# SCH_sir-kodic_2026-05-30.net
KiCad netlist of a schematic drawn in EasyEDA
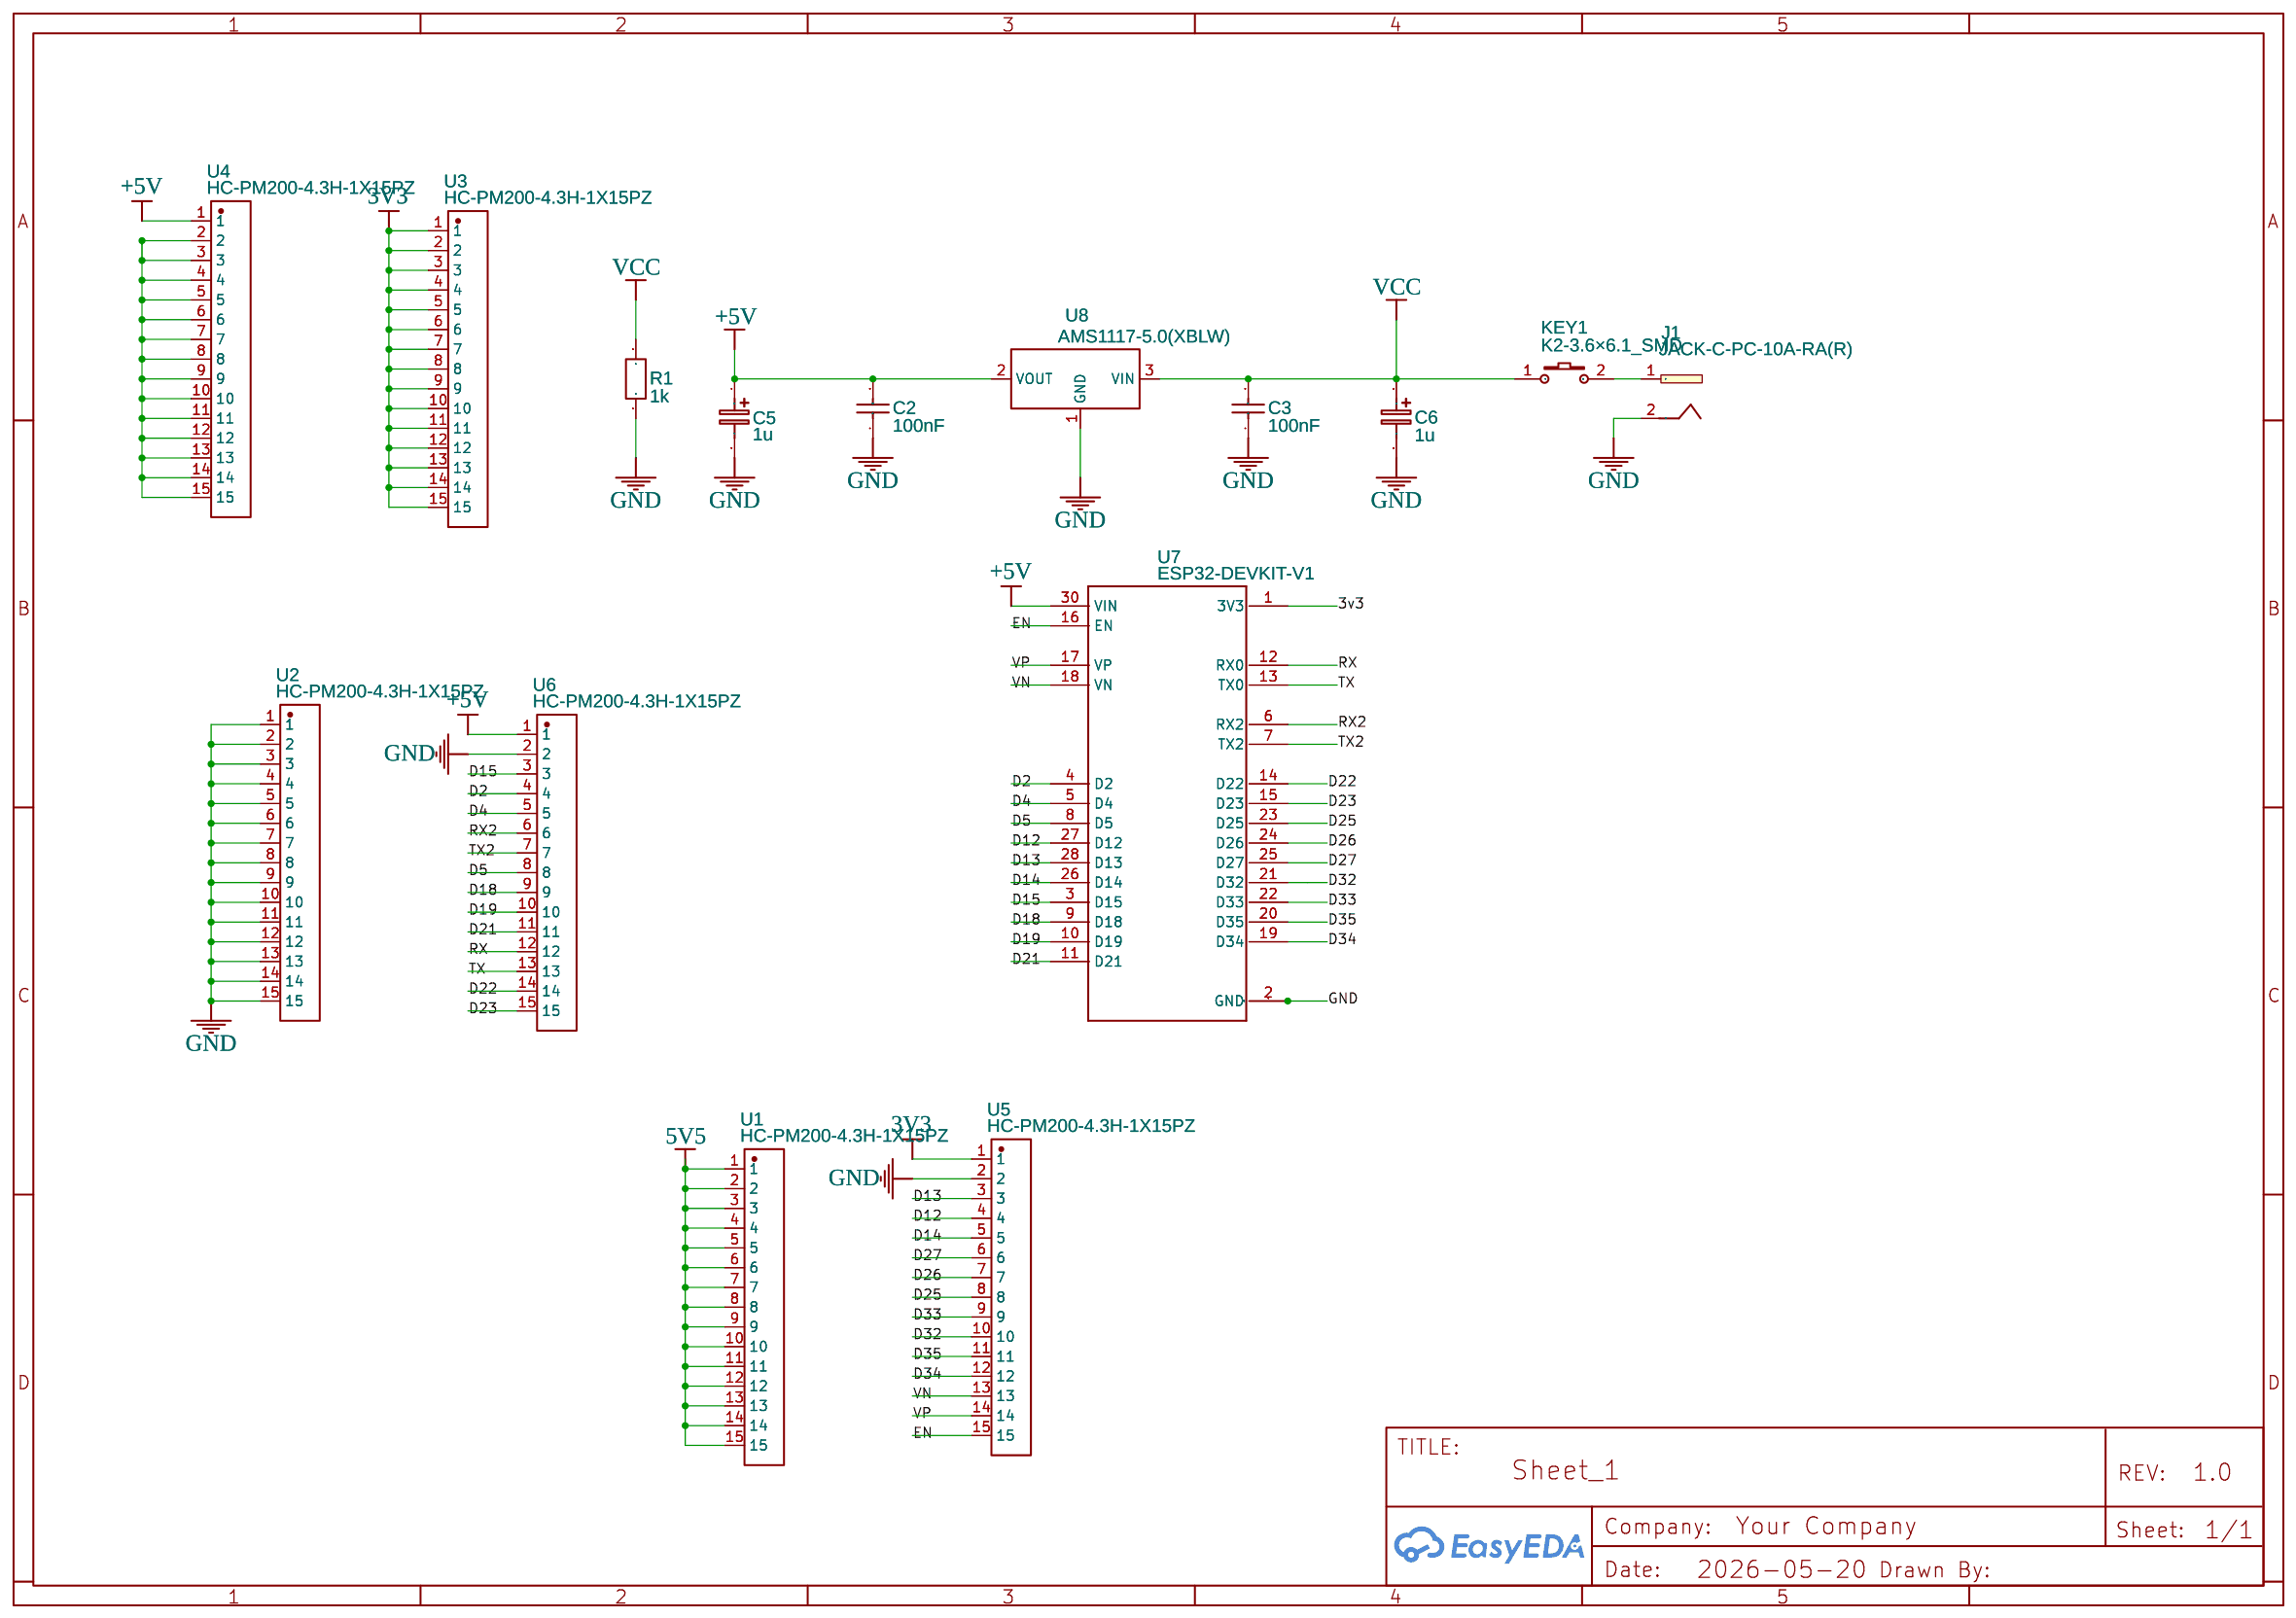
[diagram p0: schematic sheet]

(export (version "E")
  (design (tool "Eeschema 10.0.6"))
  (components
    (comp (ref "C2")
      (value "100nF")
      (fields (field (name "Manufacturer Part") "0.1UF(104) +-20% 63v"))
      (libsource (lib "") (part "100nF"))
    )
    (comp (ref "C3")
      (value "100nF")
      (fields (field (name "Manufacturer Part") "0.1UF(104) +-20% 63v"))
      (libsource (lib "") (part "100nF"))
    )
    (comp (ref "C5") (value "1u") (libsource (lib "") (part "C_Tan_SMD_A_EU")))
    (comp (ref "C6") (value "1u") (libsource (lib "") (part "C_Tan_SMD_A_EU_1")))
    (comp (ref "J1") (value "JACK-C-PC-10A-RA(R)") (libsource (lib "") (part "JACK-C-PC-10A-RA(R)")))
    (comp (ref "KEY1")
      (value "K2-3.6×6.1_SMD")
      (fields (field (name "Manufacturer Part") "K2-1107ST-A4SW-06"))
      (libsource (lib "") (part "K2-3.6×6.1_SMD"))
    )
    (comp (ref "R1") (value "1k") (libsource (lib "") (part "R_0603_EU")))
    (comp (ref "U1")
      (value "HC-PM200-4.3H-1X15PZ")
      (fields
        (field (name "Manufacturer Part") "HC-PM200-4.3H-1x15PZ")
        (field (name "Manufacturer") "HC(虹成电子)")
      )
      (libsource (lib "") (part "HC-PM200-4.3H-1X15PZ"))
    )
    (comp (ref "U2")
      (value "HC-PM200-4.3H-1X15PZ")
      (fields
        (field (name "Manufacturer Part") "HC-PM200-4.3H-1x15PZ")
        (field (name "Manufacturer") "HC(虹成电子)")
      )
      (libsource (lib "") (part "HC-PM200-4.3H-1X15PZ"))
    )
    (comp (ref "U3")
      (value "HC-PM200-4.3H-1X15PZ")
      (fields
        (field (name "Manufacturer Part") "HC-PM200-4.3H-1x15PZ")
        (field (name "Manufacturer") "HC(虹成电子)")
      )
      (libsource (lib "") (part "HC-PM200-4.3H-1X15PZ"))
    )
    (comp (ref "U4")
      (value "HC-PM200-4.3H-1X15PZ")
      (fields
        (field (name "Manufacturer Part") "HC-PM200-4.3H-1x15PZ")
        (field (name "Manufacturer") "HC(虹成电子)")
      )
      (libsource (lib "") (part "HC-PM200-4.3H-1X15PZ"))
    )
    (comp (ref "U5")
      (value "HC-PM200-4.3H-1X15PZ")
      (fields
        (field (name "Manufacturer Part") "HC-PM200-4.3H-1x15PZ")
        (field (name "Manufacturer") "HC(虹成电子)")
      )
      (libsource (lib "") (part "HC-PM200-4.3H-1X15PZ"))
    )
    (comp (ref "U6")
      (value "HC-PM200-4.3H-1X15PZ")
      (fields
        (field (name "Manufacturer Part") "HC-PM200-4.3H-1x15PZ")
        (field (name "Manufacturer") "HC(虹成电子)")
      )
      (libsource (lib "") (part "HC-PM200-4.3H-1X15PZ"))
    )
    (comp (ref "U7") (value "ESP32-DEVKIT-V1") (libsource (lib "") (part "ESP32-DEVKIT-V1")))
    (comp (ref "U8")
      (value "AMS1117-5.0(XBLW)")
      (fields (field (name "Manufacturer") "XBLW(芯伯乐)"))
      (libsource (lib "") (part "AMS1117-5.0(XBLW)"))
    )
  )
  (nets
    (net (code "1") (name "+5V") (class "Default")
      (node (ref "C2") (pin "2") (pinfunction "2_2") (pintype "input"))
      (node (ref "C5") (pin "1") (pinfunction "1_1") (pintype "unspecified"))
      (node (ref "U4") (pin "1") (pinfunction "1_1") (pintype "unspecified"))
      (node (ref "U6") (pin "1") (pinfunction "1_1") (pintype "unspecified"))
      (node (ref "U7") (pin "30") (pinfunction "VIN_30") (pintype "bidirectional"))
      (node (ref "U8") (pin "2") (pinfunction "VOUT_2") (pintype "unspecified"))
    )
    (net (code "2") (name "/3v3") (class "Default")
      (node (ref "U7") (pin "1") (pinfunction "3V3_1") (pintype "bidirectional"))
    )
    (net (code "3") (name "/D2") (class "Default")
      (node (ref "U6") (pin "4") (pinfunction "4_4") (pintype "unspecified"))
      (node (ref "U7") (pin "4") (pinfunction "D2_4") (pintype "bidirectional"))
    )
    (net (code "4") (name "/D4") (class "Default")
      (node (ref "U6") (pin "5") (pinfunction "5_5") (pintype "unspecified"))
      (node (ref "U7") (pin "5") (pinfunction "D4_5") (pintype "bidirectional"))
    )
    (net (code "5") (name "/D5") (class "Default")
      (node (ref "U6") (pin "8") (pinfunction "8_8") (pintype "unspecified"))
      (node (ref "U7") (pin "8") (pinfunction "D5_8") (pintype "bidirectional"))
    )
    (net (code "6") (name "/D12") (class "Default")
      (node (ref "U5") (pin "4") (pinfunction "4_4") (pintype "unspecified"))
      (node (ref "U7") (pin "27") (pinfunction "D12_27") (pintype "bidirectional"))
    )
    (net (code "7") (name "/D13") (class "Default")
      (node (ref "U5") (pin "3") (pinfunction "3_3") (pintype "unspecified"))
      (node (ref "U7") (pin "28") (pinfunction "D13_28") (pintype "bidirectional"))
    )
    (net (code "8") (name "/D14") (class "Default")
      (node (ref "U5") (pin "5") (pinfunction "5_5") (pintype "unspecified"))
      (node (ref "U7") (pin "26") (pinfunction "D14_26") (pintype "bidirectional"))
    )
    (net (code "9") (name "/D15") (class "Default")
      (node (ref "U6") (pin "3") (pinfunction "3_3") (pintype "unspecified"))
      (node (ref "U7") (pin "3") (pinfunction "D15_3") (pintype "bidirectional"))
    )
    (net (code "10") (name "/D18") (class "Default")
      (node (ref "U6") (pin "9") (pinfunction "9_9") (pintype "unspecified"))
      (node (ref "U7") (pin "9") (pinfunction "D18_9") (pintype "bidirectional"))
    )
    (net (code "11") (name "/D19") (class "Default")
      (node (ref "U6") (pin "10") (pinfunction "10_10") (pintype "unspecified"))
      (node (ref "U7") (pin "10") (pinfunction "D19_10") (pintype "bidirectional"))
    )
    (net (code "12") (name "/D21") (class "Default")
      (node (ref "U6") (pin "11") (pinfunction "11_11") (pintype "unspecified"))
      (node (ref "U7") (pin "11") (pinfunction "D21_11") (pintype "bidirectional"))
    )
    (net (code "13") (name "/D22") (class "Default")
      (node (ref "U6") (pin "14") (pinfunction "14_14") (pintype "unspecified"))
      (node (ref "U7") (pin "14") (pinfunction "D22_14") (pintype "bidirectional"))
    )
    (net (code "14") (name "/D23") (class "Default")
      (node (ref "U6") (pin "15") (pinfunction "15_15") (pintype "unspecified"))
      (node (ref "U7") (pin "15") (pinfunction "D23_15") (pintype "bidirectional"))
    )
    (net (code "15") (name "/D25") (class "Default")
      (node (ref "U5") (pin "8") (pinfunction "8_8") (pintype "unspecified"))
      (node (ref "U7") (pin "23") (pinfunction "D25_23") (pintype "bidirectional"))
    )
    (net (code "16") (name "/D26") (class "Default")
      (node (ref "U5") (pin "7") (pinfunction "7_7") (pintype "unspecified"))
      (node (ref "U7") (pin "24") (pinfunction "D26_24") (pintype "bidirectional"))
    )
    (net (code "17") (name "/D27") (class "Default")
      (node (ref "U5") (pin "6") (pinfunction "6_6") (pintype "unspecified"))
      (node (ref "U7") (pin "25") (pinfunction "D27_25") (pintype "bidirectional"))
    )
    (net (code "18") (name "/D32") (class "Default")
      (node (ref "U5") (pin "10") (pinfunction "10_10") (pintype "unspecified"))
      (node (ref "U7") (pin "21") (pinfunction "D32_21") (pintype "bidirectional"))
    )
    (net (code "19") (name "/D33") (class "Default")
      (node (ref "U5") (pin "9") (pinfunction "9_9") (pintype "unspecified"))
      (node (ref "U7") (pin "22") (pinfunction "D33_22") (pintype "bidirectional"))
    )
    (net (code "20") (name "/D34") (class "Default")
      (node (ref "U5") (pin "12") (pinfunction "12_12") (pintype "unspecified"))
      (node (ref "U7") (pin "19") (pinfunction "D34_19") (pintype "bidirectional"))
    )
    (net (code "21") (name "/D35") (class "Default")
      (node (ref "U5") (pin "11") (pinfunction "11_11") (pintype "unspecified"))
      (node (ref "U7") (pin "20") (pinfunction "D35_20") (pintype "bidirectional"))
    )
    (net (code "22") (name "/EN") (class "Default")
      (node (ref "U5") (pin "15") (pinfunction "15_15") (pintype "unspecified"))
      (node (ref "U7") (pin "16") (pinfunction "EN_16") (pintype "bidirectional"))
    )
    (net (code "23") (name "/RX") (class "Default")
      (node (ref "U6") (pin "12") (pinfunction "12_12") (pintype "unspecified"))
      (node (ref "U7") (pin "12") (pinfunction "RX0_12") (pintype "bidirectional"))
    )
    (net (code "24") (name "/RX2") (class "Default")
      (node (ref "U6") (pin "6") (pinfunction "6_6") (pintype "unspecified"))
      (node (ref "U7") (pin "6") (pinfunction "RX2_6") (pintype "bidirectional"))
    )
    (net (code "25") (name "/TX") (class "Default")
      (node (ref "U6") (pin "13") (pinfunction "13_13") (pintype "unspecified"))
      (node (ref "U7") (pin "13") (pinfunction "TX0_13") (pintype "bidirectional"))
    )
    (net (code "26") (name "/TX2") (class "Default")
      (node (ref "U6") (pin "7") (pinfunction "7_7") (pintype "unspecified"))
      (node (ref "U7") (pin "7") (pinfunction "TX2_7") (pintype "bidirectional"))
    )
    (net (code "27") (name "/VN") (class "Default")
      (node (ref "U5") (pin "13") (pinfunction "13_13") (pintype "unspecified"))
      (node (ref "U7") (pin "18") (pinfunction "VN_18") (pintype "bidirectional"))
    )
    (net (code "28") (name "/VP") (class "Default")
      (node (ref "U5") (pin "14") (pinfunction "14_14") (pintype "unspecified"))
      (node (ref "U7") (pin "17") (pinfunction "VP_17") (pintype "bidirectional"))
    )
    (net (code "29") (name "3V3") (class "Default")
      (node (ref "U3") (pin "1") (pinfunction "1_1") (pintype "unspecified"))
      (node (ref "U3") (pin "10") (pinfunction "10_10") (pintype "unspecified"))
      (node (ref "U3") (pin "11") (pinfunction "11_11") (pintype "unspecified"))
      (node (ref "U3") (pin "12") (pinfunction "12_12") (pintype "unspecified"))
      (node (ref "U3") (pin "13") (pinfunction "13_13") (pintype "unspecified"))
      (node (ref "U3") (pin "14") (pinfunction "14_14") (pintype "unspecified"))
      (node (ref "U3") (pin "15") (pinfunction "15_15") (pintype "unspecified"))
      (node (ref "U3") (pin "2") (pinfunction "2_2") (pintype "unspecified"))
      (node (ref "U3") (pin "3") (pinfunction "3_3") (pintype "unspecified"))
      (node (ref "U3") (pin "4") (pinfunction "4_4") (pintype "unspecified"))
      (node (ref "U3") (pin "5") (pinfunction "5_5") (pintype "unspecified"))
      (node (ref "U3") (pin "6") (pinfunction "6_6") (pintype "unspecified"))
      (node (ref "U3") (pin "7") (pinfunction "7_7") (pintype "unspecified"))
      (node (ref "U3") (pin "8") (pinfunction "8_8") (pintype "unspecified"))
      (node (ref "U3") (pin "9") (pinfunction "9_9") (pintype "unspecified"))
      (node (ref "U5") (pin "1") (pinfunction "1_1") (pintype "unspecified"))
    )
    (net (code "30") (name "5V5") (class "Default")
      (node (ref "U1") (pin "1") (pinfunction "1_1") (pintype "unspecified"))
      (node (ref "U1") (pin "10") (pinfunction "10_10") (pintype "unspecified"))
      (node (ref "U1") (pin "11") (pinfunction "11_11") (pintype "unspecified"))
      (node (ref "U1") (pin "12") (pinfunction "12_12") (pintype "unspecified"))
      (node (ref "U1") (pin "13") (pinfunction "13_13") (pintype "unspecified"))
      (node (ref "U1") (pin "14") (pinfunction "14_14") (pintype "unspecified"))
      (node (ref "U1") (pin "15") (pinfunction "15_15") (pintype "unspecified"))
      (node (ref "U1") (pin "2") (pinfunction "2_2") (pintype "unspecified"))
      (node (ref "U1") (pin "3") (pinfunction "3_3") (pintype "unspecified"))
      (node (ref "U1") (pin "4") (pinfunction "4_4") (pintype "unspecified"))
      (node (ref "U1") (pin "5") (pinfunction "5_5") (pintype "unspecified"))
      (node (ref "U1") (pin "6") (pinfunction "6_6") (pintype "unspecified"))
      (node (ref "U1") (pin "7") (pinfunction "7_7") (pintype "unspecified"))
      (node (ref "U1") (pin "8") (pinfunction "8_8") (pintype "unspecified"))
      (node (ref "U1") (pin "9") (pinfunction "9_9") (pintype "unspecified"))
    )
    (net (code "31") (name "GND") (class "Default")
      (node (ref "C2") (pin "1") (pinfunction "1_1") (pintype "input"))
      (node (ref "C3") (pin "1") (pinfunction "1_1") (pintype "input"))
      (node (ref "C5") (pin "2") (pinfunction "2_2") (pintype "unspecified"))
      (node (ref "C6") (pin "2") (pinfunction "2_2") (pintype "unspecified"))
      (node (ref "J1") (pin "2") (pinfunction "2_2") (pintype "bidirectional"))
      (node (ref "R1") (pin "1") (pinfunction "1_1") (pintype "unspecified"))
      (node (ref "U2") (pin "1") (pinfunction "1_1") (pintype "unspecified"))
      (node (ref "U2") (pin "10") (pinfunction "10_10") (pintype "unspecified"))
      (node (ref "U2") (pin "11") (pinfunction "11_11") (pintype "unspecified"))
      (node (ref "U2") (pin "12") (pinfunction "12_12") (pintype "unspecified"))
      (node (ref "U2") (pin "13") (pinfunction "13_13") (pintype "unspecified"))
      (node (ref "U2") (pin "14") (pinfunction "14_14") (pintype "unspecified"))
      (node (ref "U2") (pin "15") (pinfunction "15_15") (pintype "unspecified"))
      (node (ref "U2") (pin "2") (pinfunction "2_2") (pintype "unspecified"))
      (node (ref "U2") (pin "3") (pinfunction "3_3") (pintype "unspecified"))
      (node (ref "U2") (pin "4") (pinfunction "4_4") (pintype "unspecified"))
      (node (ref "U2") (pin "5") (pinfunction "5_5") (pintype "unspecified"))
      (node (ref "U2") (pin "6") (pinfunction "6_6") (pintype "unspecified"))
      (node (ref "U2") (pin "7") (pinfunction "7_7") (pintype "unspecified"))
      (node (ref "U2") (pin "8") (pinfunction "8_8") (pintype "unspecified"))
      (node (ref "U2") (pin "9") (pinfunction "9_9") (pintype "unspecified"))
      (node (ref "U5") (pin "2") (pinfunction "2_2") (pintype "unspecified"))
      (node (ref "U6") (pin "2") (pinfunction "2_2") (pintype "unspecified"))
      (node (ref "U7") (pin "2") (pinfunction "GND_2") (pintype "bidirectional"))
      (node (ref "U7") (pin "29") (pinfunction "GND_29") (pintype "bidirectional"))
      (node (ref "U8") (pin "1") (pinfunction "GND_1") (pintype "unspecified"))
    )
    (net (code "32") (name "Net-(J1-Pad1)") (class "Default")
      (node (ref "J1") (pin "1") (pinfunction "1_1") (pintype "bidirectional"))
      (node (ref "KEY1") (pin "2") (pinfunction "2_2") (pintype "unspecified"))
    )
    (net (code "33") (name "Net-(U4-Pad10)") (class "Default")
      (node (ref "U4") (pin "10") (pinfunction "10_10") (pintype "unspecified"))
      (node (ref "U4") (pin "11") (pinfunction "11_11") (pintype "unspecified"))
      (node (ref "U4") (pin "12") (pinfunction "12_12") (pintype "unspecified"))
      (node (ref "U4") (pin "13") (pinfunction "13_13") (pintype "unspecified"))
      (node (ref "U4") (pin "14") (pinfunction "14_14") (pintype "unspecified"))
      (node (ref "U4") (pin "15") (pinfunction "15_15") (pintype "unspecified"))
      (node (ref "U4") (pin "2") (pinfunction "2_2") (pintype "unspecified"))
      (node (ref "U4") (pin "3") (pinfunction "3_3") (pintype "unspecified"))
      (node (ref "U4") (pin "4") (pinfunction "4_4") (pintype "unspecified"))
      (node (ref "U4") (pin "5") (pinfunction "5_5") (pintype "unspecified"))
      (node (ref "U4") (pin "6") (pinfunction "6_6") (pintype "unspecified"))
      (node (ref "U4") (pin "7") (pinfunction "7_7") (pintype "unspecified"))
      (node (ref "U4") (pin "8") (pinfunction "8_8") (pintype "unspecified"))
      (node (ref "U4") (pin "9") (pinfunction "9_9") (pintype "unspecified"))
    )
    (net (code "34") (name "VCC") (class "Default")
      (node (ref "C3") (pin "2") (pinfunction "2_2") (pintype "input"))
      (node (ref "C6") (pin "1") (pinfunction "1_1") (pintype "unspecified"))
      (node (ref "KEY1") (pin "1") (pinfunction "1_1") (pintype "unspecified"))
      (node (ref "R1") (pin "2") (pinfunction "2_2") (pintype "unspecified"))
      (node (ref "U8") (pin "3") (pinfunction "VIN_3") (pintype "unspecified"))
    )
  )
)
